# Sheet1.net
KiCad netlist of a schematic drawn in Altium Designer
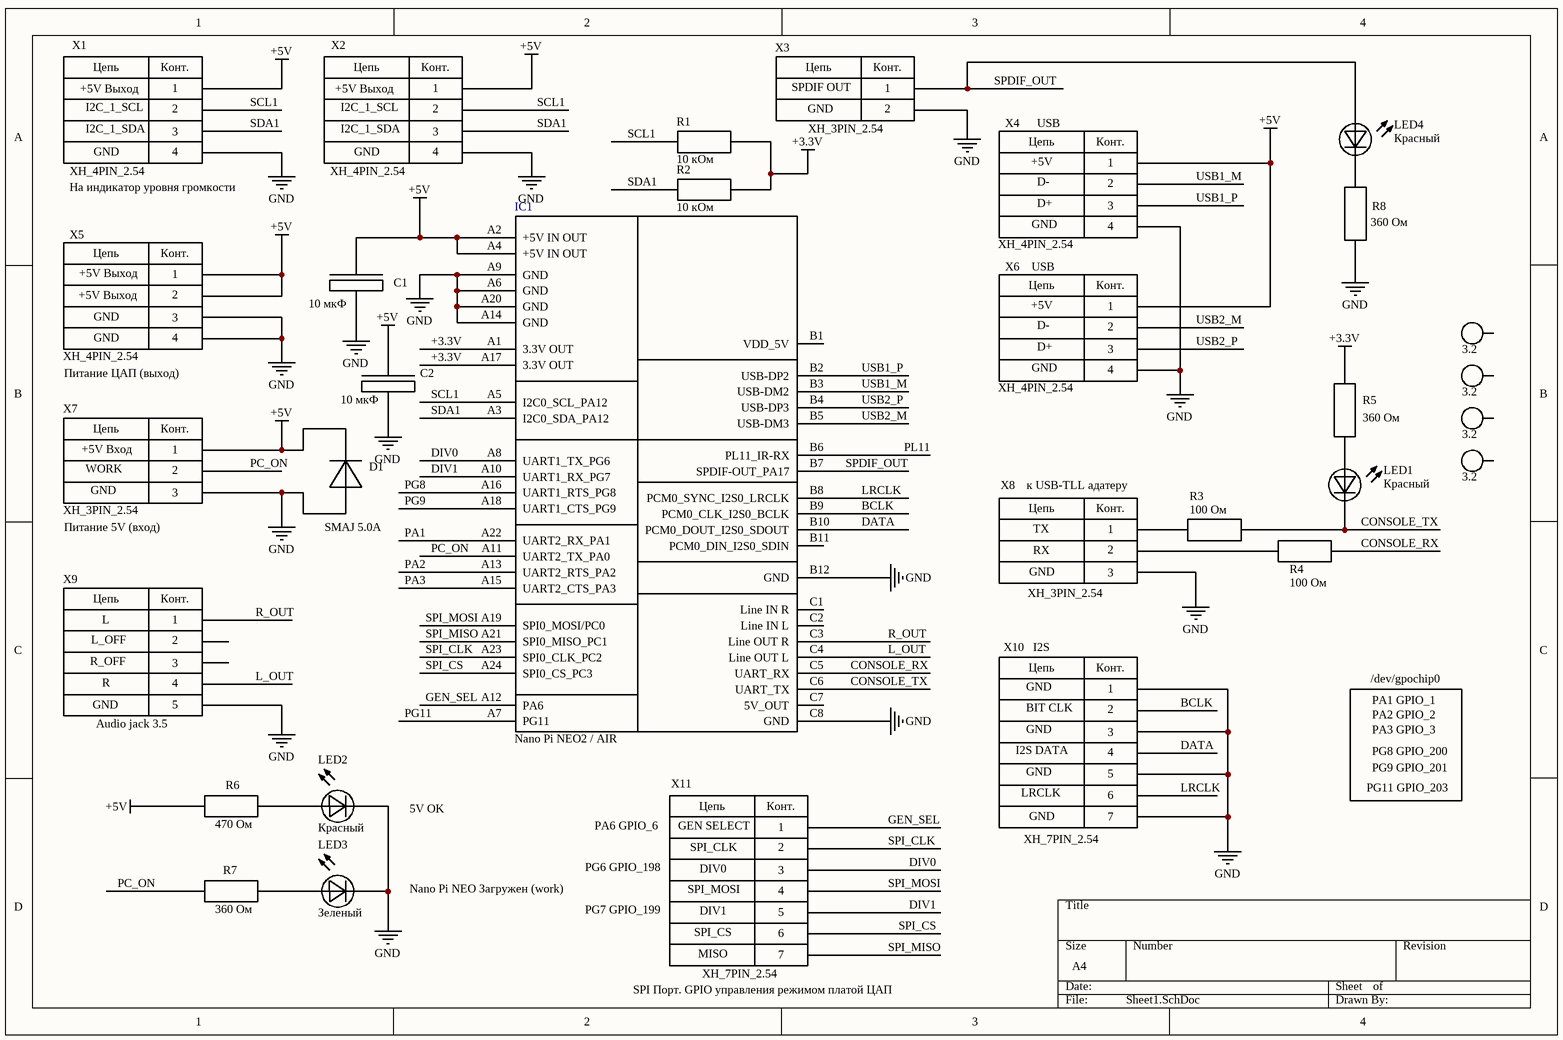
[diagram p0: Sheet1.SchDoc]

(export (version "E")
  (design (tool "Eeschema 10.0.6"))
  (components
    (comp (ref "C1")
      (value "10 мкФ")
      (footprint "Конденсатор SMD тантал 4x7")
      (libsource (lib "S83") (part "Конденсатор"))
    )
    (comp (ref "C2")
      (value "10 мкФ")
      (footprint "Конденсатор SMD тантал 4x7")
      (libsource (lib "S83") (part "Конденсатор"))
    )
    (comp (ref "D1") (value "SMAJ 5.0A") (footprint "Диод SS14") (libsource (lib "S83") (part "Диод")))
    (comp (ref "H1")
      (value "3.2")
      (footprint "Отверстие 3,2")
      (libsource (lib "S83") (part "Отверстие монтажное"))
    )
    (comp (ref "H2")
      (value "3.2")
      (footprint "Отверстие 3,2")
      (libsource (lib "S83") (part "Отверстие монтажное"))
    )
    (comp (ref "H3")
      (value "3.2")
      (footprint "Отверстие 3,2")
      (libsource (lib "S83") (part "Отверстие монтажное"))
    )
    (comp (ref "H4")
      (value "3.2")
      (footprint "Отверстие 3,2")
      (libsource (lib "S83") (part "Отверстие монтажное"))
    )
    (comp (ref "IC1")
      (value "Nano Pi NEO2 / AIR")
      (footprint "NANOPI_NEO")
      (libsource (lib "S83_IC") (part "NanoPi NEO"))
    )
    (comp (ref "LED1")
      (value "Красный")
      (footprint "Светодиод 3mm")
      (libsource (lib "S83") (part "Светодиод"))
    )
    (comp (ref "LED2")
      (value "Красный")
      (footprint "Светодиод 3mm")
      (libsource (lib "S83") (part "Светодиод"))
    )
    (comp (ref "LED3")
      (value "Зеленый")
      (footprint "Светодиод 3mm")
      (libsource (lib "S83") (part "Светодиод"))
    )
    (comp (ref "LED4")
      (value "Красный")
      (footprint "Светодиод 3mm")
      (libsource (lib "S83") (part "Светодиод"))
    )
    (comp (ref "R1")
      (value "10 кОм")
      (footprint "SMD 1206 Резистор")
      (libsource (lib "S83") (part "Резистор"))
    )
    (comp (ref "R2")
      (value "10 кОм")
      (footprint "SMD 1206 Резистор")
      (libsource (lib "S83") (part "Резистор"))
    )
    (comp (ref "R3")
      (value "100 Ом")
      (footprint "SMD 1206 Резистор")
      (libsource (lib "S83") (part "Резистор"))
    )
    (comp (ref "R4")
      (value "100 Ом")
      (footprint "SMD 1206 Резистор")
      (libsource (lib "S83") (part "Резистор"))
    )
    (comp (ref "R5")
      (value "360 Ом")
      (footprint "SMD 1206 Резистор")
      (libsource (lib "S83") (part "Резистор"))
    )
    (comp (ref "R6")
      (value "470 Ом")
      (footprint "SMD 1206 Резистор")
      (libsource (lib "S83") (part "Резистор"))
    )
    (comp (ref "R7")
      (value "360 Ом")
      (footprint "SMD 1206 Резистор")
      (libsource (lib "S83") (part "Резистор"))
    )
    (comp (ref "R8")
      (value "360 Ом")
      (footprint "SMD 1206 Резистор")
      (libsource (lib "S83") (part "Резистор"))
    )
    (comp (ref "X1")
      (value "XH_4PIN_2.54")
      (footprint "(1x4) PIN XH 2.54 HEADR")
      (libsource (lib "S83_connectors") (part "(1x4) pin XH 2.54 Header"))
    )
    (comp (ref "X2")
      (value "XH_4PIN_2.54")
      (footprint "(1x4) PIN XH 2.54 HEADR")
      (libsource (lib "S83_connectors") (part "(1x4) pin XH 2.54 Header"))
    )
    (comp (ref "X3")
      (value "XH_3PIN_2.54")
      (footprint "(1x2) PIN XH 2.54 header")
      (libsource (lib "S83_connectors") (part "(1x2)pin 2.54 Header"))
    )
    (comp (ref "X4")
      (value "XH_4PIN_2.54")
      (footprint "(1x4) PIN XH 2.54 HEADR")
      (libsource (lib "S83_connectors") (part "(1x4) pin XH 2.54 Header"))
    )
    (comp (ref "X5")
      (value "XH_4PIN_2.54")
      (footprint "(1x4) PIN XH 2.54 HEADR")
      (libsource (lib "S83_connectors") (part "(1x4) pin XH 2.54 Header"))
    )
    (comp (ref "X6")
      (value "XH_4PIN_2.54")
      (footprint "(1x4) PIN XH 2.54 HEADR")
      (libsource (lib "S83_connectors") (part "(1x4) pin XH 2.54 Header"))
    )
    (comp (ref "X7")
      (value "XH_3PIN_2.54")
      (footprint "(1x3) PIN XH 2.54 HEADR")
      (libsource (lib "S83_connectors") (part "(1x3)pin 2.54 Header"))
    )
    (comp (ref "X8")
      (value "XH_3PIN_2.54")
      (footprint "(1x3) PIN XH 2.54 HEADR")
      (libsource (lib "S83_connectors") (part "(1x3)pin 2.54 Header"))
    )
    (comp (ref "X9")
      (value "Audio jack 3.5")
      (footprint "3.5 Audio jack mama")
      (libsource (lib "S83_connectors") (part "3.5 Audio"))
    )
    (comp (ref "X10")
      (value "XH_7PIN_2.54")
      (footprint "(1x7) PIN XH 2.54 HEADR")
      (libsource (lib "S83_connectors") (part "(1x7) pin 2.54 Header"))
    )
    (comp (ref "X11")
      (value "XH_7PIN_2.54")
      (footprint "(1x7) PIN XH 2.54 HEADR")
      (libsource (lib "S83_connectors") (part "(1x7) pin 2.54 Header"))
    )
  )
  (nets
    (net (code "1") (name "+3.3V") (class "Default")
      (node (ref "IC1") (pin "A1") (pinfunction "3.3V_OUT_A1") (pintype "passive"))
      (node (ref "IC1") (pin "A17") (pinfunction "3.3V_OUT_A17") (pintype "passive"))
      (node (ref "R1") (pin "1") (pinfunction "left_1") (pintype "passive"))
      (node (ref "R2") (pin "1") (pinfunction "left_1") (pintype "passive"))
      (node (ref "R5") (pin "1") (pinfunction "left_1") (pintype "passive"))
    )
    (net (code "2") (name "+5V") (class "Default")
      (node (ref "C1") (pin "1") (pinfunction "1_1") (pintype "passive"))
      (node (ref "C2") (pin "1") (pinfunction "1_1") (pintype "passive"))
      (node (ref "D1") (pin "2") (pinfunction "K_2") (pintype "passive"))
      (node (ref "IC1") (pin "A2") (pinfunction "+5V_IN_OUT_A2") (pintype "passive"))
      (node (ref "IC1") (pin "A4") (pinfunction "+5V_IN_OUT_A4") (pintype "passive"))
      (node (ref "R6") (pin "2") (pinfunction "right_2") (pintype "passive"))
      (node (ref "X1") (pin "1") (pinfunction "1_1") (pintype "passive"))
      (node (ref "X2") (pin "1") (pinfunction "1_1") (pintype "passive"))
      (node (ref "X4") (pin "1") (pinfunction "1_1") (pintype "passive"))
      (node (ref "X5") (pin "1") (pinfunction "1_1") (pintype "passive"))
      (node (ref "X5") (pin "2") (pinfunction "2_2") (pintype "passive"))
      (node (ref "X6") (pin "1") (pinfunction "1_1") (pintype "passive"))
      (node (ref "X7") (pin "1") (pinfunction "1_1") (pintype "passive"))
    )
    (net (code "3") (name "/BCLK") (class "Default")
      (node (ref "IC1") (pin "B9") (pinfunction "PCM0_CLK_I2S0_BCLK_B9") (pintype "passive"))
      (node (ref "X10") (pin "2") (pinfunction "2_2") (pintype "passive"))
    )
    (net (code "4") (name "/CONSOLE_RX") (class "Default")
      (node (ref "IC1") (pin "C5") (pinfunction "UART_RX_C5") (pintype "passive"))
      (node (ref "R4") (pin "1") (pinfunction "left_1") (pintype "passive"))
    )
    (net (code "5") (name "/CONSOLE_TX") (class "Default")
      (node (ref "IC1") (pin "C6") (pinfunction "UART_TX_C6") (pintype "passive"))
      (node (ref "LED1") (pin "2") (pinfunction "K_2") (pintype "passive"))
      (node (ref "R3") (pin "1") (pinfunction "left_1") (pintype "passive"))
    )
    (net (code "8") (name "/DATA") (class "Default")
      (node (ref "IC1") (pin "B10") (pinfunction "PCM0_DOUT_I2S0_SDOUT_B10") (pintype "passive"))
      (node (ref "X10") (pin "4") (pinfunction "4_4") (pintype "passive"))
    )
    (net (code "9") (name "/DIV0") (class "Default")
      (node (ref "IC1") (pin "A8") (pinfunction "UART1_TX_PG6_A8") (pintype "passive"))
      (node (ref "X11") (pin "3") (pinfunction "3_3") (pintype "passive"))
    )
    (net (code "10") (name "/DIV1") (class "Default")
      (node (ref "IC1") (pin "A10") (pinfunction "UART1_RX_PG7_A10") (pintype "passive"))
      (node (ref "X11") (pin "5") (pinfunction "5_5") (pintype "passive"))
    )
    (net (code "11") (name "/GEN_SEL") (class "Default")
      (node (ref "IC1") (pin "A12") (pinfunction "PA6_A12") (pintype "passive"))
      (node (ref "X11") (pin "1") (pinfunction "1_1") (pintype "passive"))
    )
    (net (code "14") (name "/LRCLK") (class "Default")
      (node (ref "IC1") (pin "B8") (pinfunction "PCM0_SYNC_I2S0_LRCLK_B8") (pintype "passive"))
      (node (ref "X10") (pin "6") (pinfunction "6_6") (pintype "passive"))
    )
    (net (code "15") (name "/L_OUT") (class "Default")
      (node (ref "IC1") (pin "C4") (pinfunction "Line_OUT_L_C4") (pintype "passive"))
      (node (ref "X9") (pin "4") (pinfunction "4_4") (pintype "passive"))
    )
    (net (code "16") (name "/PA1") (class "Default")
      (node (ref "IC1") (pin "A22") (pinfunction "UART2_RX_PA1_A22") (pintype "passive"))
    )
    (net (code "17") (name "/PA2") (class "Default")
      (node (ref "IC1") (pin "A13") (pinfunction "UART2_RTS_PA2_A13") (pintype "passive"))
    )
    (net (code "18") (name "/PA3") (class "Default")
      (node (ref "IC1") (pin "A15") (pinfunction "UART2_CTS_PA3_A15") (pintype "passive"))
    )
    (net (code "19") (name "/PC_ON") (class "Default")
      (node (ref "IC1") (pin "A11") (pinfunction "UART2_TX_PA0_A11") (pintype "passive"))
      (node (ref "R7") (pin "2") (pinfunction "right_2") (pintype "passive"))
      (node (ref "X7") (pin "2") (pinfunction "2_2") (pintype "passive"))
    )
    (net (code "20") (name "/PG8") (class "Default")
      (node (ref "IC1") (pin "A16") (pinfunction "UART1_RTS_PG8_A16") (pintype "passive"))
    )
    (net (code "21") (name "/PG9") (class "Default")
      (node (ref "IC1") (pin "A18") (pinfunction "UART1_CTS_PG9_A18") (pintype "passive"))
    )
    (net (code "22") (name "/PG11") (class "Default")
      (node (ref "IC1") (pin "A7") (pinfunction "PG11_A7") (pintype "passive"))
    )
    (net (code "23") (name "/PL11") (class "Default")
      (node (ref "IC1") (pin "B6") (pinfunction "PL11_IR-RX_B6") (pintype "passive"))
    )
    (net (code "24") (name "/R_OUT") (class "Default")
      (node (ref "IC1") (pin "C3") (pinfunction "Line_OUT_R_C3") (pintype "passive"))
      (node (ref "X9") (pin "1") (pinfunction "1_1") (pintype "passive"))
    )
    (net (code "25") (name "/SCL1") (class "Default")
      (node (ref "IC1") (pin "A5") (pinfunction "I2C0_SCL_PA12_A5") (pintype "passive"))
      (node (ref "R1") (pin "2") (pinfunction "right_2") (pintype "passive"))
      (node (ref "X1") (pin "2") (pinfunction "2_2") (pintype "passive"))
      (node (ref "X2") (pin "2") (pinfunction "2_2") (pintype "passive"))
    )
    (net (code "26") (name "/SDA1") (class "Default")
      (node (ref "IC1") (pin "A3") (pinfunction "I2C0_SDA_PA12_A3") (pintype "passive"))
      (node (ref "R2") (pin "2") (pinfunction "right_2") (pintype "passive"))
      (node (ref "X1") (pin "3") (pinfunction "3_3") (pintype "passive"))
      (node (ref "X2") (pin "3") (pinfunction "3_3") (pintype "passive"))
    )
    (net (code "27") (name "/SPDIF_OUT") (class "Default")
      (node (ref "IC1") (pin "B7") (pinfunction "SPDIF-OUT_PA17_B7") (pintype "passive"))
      (node (ref "LED4") (pin "1") (pinfunction "А_1") (pintype "passive"))
      (node (ref "X3") (pin "1") (pinfunction "1_1") (pintype "passive"))
    )
    (net (code "28") (name "/SPI_CLK") (class "Default")
      (node (ref "IC1") (pin "A23") (pinfunction "SPI0_CLK_PC2_A23") (pintype "passive"))
      (node (ref "X11") (pin "2") (pinfunction "2_2") (pintype "passive"))
    )
    (net (code "29") (name "/SPI_CS") (class "Default")
      (node (ref "IC1") (pin "A24") (pinfunction "SPI0_CS_PC3_A24") (pintype "passive"))
      (node (ref "X11") (pin "6") (pinfunction "6_6") (pintype "passive"))
    )
    (net (code "30") (name "/SPI_MISO") (class "Default")
      (node (ref "IC1") (pin "A21") (pinfunction "SPI0_MISO_PC1_A21") (pintype "passive"))
      (node (ref "X11") (pin "7") (pinfunction "7_7") (pintype "passive"))
    )
    (net (code "31") (name "/SPI_MOSI") (class "Default")
      (node (ref "IC1") (pin "A19") (pinfunction "SPI0_MOSI/PС0_A19") (pintype "passive"))
      (node (ref "X11") (pin "4") (pinfunction "4_4") (pintype "passive"))
    )
    (net (code "32") (name "/USB1_M") (class "Default")
      (node (ref "IC1") (pin "B3") (pinfunction "USB-DM2_B3") (pintype "passive"))
      (node (ref "X4") (pin "2") (pinfunction "2_2") (pintype "passive"))
    )
    (net (code "33") (name "/USB1_P") (class "Default")
      (node (ref "IC1") (pin "B2") (pinfunction "USB-DP2_B2") (pintype "passive"))
      (node (ref "X4") (pin "3") (pinfunction "3_3") (pintype "passive"))
    )
    (net (code "34") (name "/USB2_M") (class "Default")
      (node (ref "IC1") (pin "B5") (pinfunction "USB-DM3_B5") (pintype "passive"))
      (node (ref "X6") (pin "2") (pinfunction "2_2") (pintype "passive"))
    )
    (net (code "35") (name "/USB2_P") (class "Default")
      (node (ref "IC1") (pin "B4") (pinfunction "USB-DP3_B4") (pintype "passive"))
      (node (ref "X6") (pin "3") (pinfunction "3_3") (pintype "passive"))
    )
    (net (code "36") (name "GND") (class "Default")
      (node (ref "C1") (pin "2") (pinfunction "2_2") (pintype "passive"))
      (node (ref "C2") (pin "2") (pinfunction "2_2") (pintype "passive"))
      (node (ref "D1") (pin "1") (pinfunction "А_1") (pintype "passive"))
      (node (ref "IC1") (pin "A14") (pinfunction "GND_A14") (pintype "passive"))
      (node (ref "IC1") (pin "A20") (pinfunction "GND_A20") (pintype "passive"))
      (node (ref "IC1") (pin "A6") (pinfunction "GND_A6") (pintype "passive"))
      (node (ref "IC1") (pin "A9") (pinfunction "GND_A9") (pintype "passive"))
      (node (ref "IC1") (pin "B12") (pinfunction "GND_B12") (pintype "passive"))
      (node (ref "IC1") (pin "C8") (pinfunction "GND_C8") (pintype "passive"))
      (node (ref "LED2") (pin "2") (pinfunction "K_2") (pintype "passive"))
      (node (ref "LED3") (pin "2") (pinfunction "K_2") (pintype "passive"))
      (node (ref "R8") (pin "2") (pinfunction "right_2") (pintype "passive"))
      (node (ref "X1") (pin "4") (pinfunction "4_4") (pintype "passive"))
      (node (ref "X10") (pin "1") (pinfunction "1_1") (pintype "passive"))
      (node (ref "X10") (pin "3") (pinfunction "3_3") (pintype "passive"))
      (node (ref "X10") (pin "5") (pinfunction "5_5") (pintype "passive"))
      (node (ref "X10") (pin "7") (pinfunction "7_7") (pintype "passive"))
      (node (ref "X2") (pin "4") (pinfunction "4_4") (pintype "passive"))
      (node (ref "X3") (pin "2") (pinfunction "2_2") (pintype "passive"))
      (node (ref "X4") (pin "4") (pinfunction "4_4") (pintype "passive"))
      (node (ref "X5") (pin "3") (pinfunction "3_3") (pintype "passive"))
      (node (ref "X5") (pin "4") (pinfunction "4_4") (pintype "passive"))
      (node (ref "X6") (pin "4") (pinfunction "4_4") (pintype "passive"))
      (node (ref "X7") (pin "3") (pinfunction "3_3") (pintype "passive"))
      (node (ref "X8") (pin "3") (pinfunction "3_3") (pintype "passive"))
      (node (ref "X9") (pin "5") (pinfunction "5_5") (pintype "passive"))
    )
    (net (code "37") (name "Net-(LED1-А)") (class "Default")
      (node (ref "LED1") (pin "1") (pinfunction "А_1") (pintype "passive"))
      (node (ref "R5") (pin "2") (pinfunction "right_2") (pintype "passive"))
    )
    (net (code "38") (name "Net-(LED2-А)") (class "Default")
      (node (ref "LED2") (pin "1") (pinfunction "А_1") (pintype "passive"))
      (node (ref "R6") (pin "1") (pinfunction "left_1") (pintype "passive"))
    )
    (net (code "39") (name "Net-(LED3-А)") (class "Default")
      (node (ref "LED3") (pin "1") (pinfunction "А_1") (pintype "passive"))
      (node (ref "R7") (pin "1") (pinfunction "left_1") (pintype "passive"))
    )
    (net (code "40") (name "Net-(LED4-K)") (class "Default")
      (node (ref "LED4") (pin "2") (pinfunction "K_2") (pintype "passive"))
      (node (ref "R8") (pin "1") (pinfunction "left_1") (pintype "passive"))
    )
    (net (code "41") (name "Net-(R3-right)") (class "Default")
      (node (ref "R3") (pin "2") (pinfunction "right_2") (pintype "passive"))
      (node (ref "X8") (pin "1") (pinfunction "1_1") (pintype "passive"))
    )
    (net (code "42") (name "Net-(R4-right)") (class "Default")
      (node (ref "R4") (pin "2") (pinfunction "right_2") (pintype "passive"))
      (node (ref "X8") (pin "2") (pinfunction "2_2") (pintype "passive"))
    )
    (net (code "43") (name "unconnected-(H1-Pad1)") (class "Default")
      (node (ref "H1") (pin "1") (pinfunction "1_1") (pintype "passive"))
    )
    (net (code "44") (name "unconnected-(H2-Pad1)") (class "Default")
      (node (ref "H2") (pin "1") (pinfunction "1_1") (pintype "passive"))
    )
    (net (code "45") (name "unconnected-(H3-Pad1)") (class "Default")
      (node (ref "H3") (pin "1") (pinfunction "1_1") (pintype "passive"))
    )
    (net (code "46") (name "unconnected-(H4-Pad1)") (class "Default")
      (node (ref "H4") (pin "1") (pinfunction "1_1") (pintype "passive"))
    )
    (net (code "47") (name "unconnected-(IC1-5V_OUT-PadC7)") (class "Default")
      (node (ref "IC1") (pin "C7") (pinfunction "5V_OUT_C7") (pintype "passive"))
    )
    (net (code "48") (name "unconnected-(IC1-Line_IN_L-PadC2)") (class "Default")
      (node (ref "IC1") (pin "C2") (pinfunction "Line_IN_L_C2") (pintype "passive"))
    )
    (net (code "49") (name "unconnected-(IC1-Line_IN_R-PadC1)") (class "Default")
      (node (ref "IC1") (pin "C1") (pinfunction "Line_IN_R_C1") (pintype "passive"))
    )
    (net (code "50") (name "unconnected-(IC1-PCM0_DIN_I2S0_SDIN-PadB11)") (class "Default")
      (node (ref "IC1") (pin "B11") (pinfunction "PCM0_DIN_I2S0_SDIN_B11") (pintype "passive"))
    )
    (net (code "51") (name "unconnected-(IC1-VDD_5V-PadB1)") (class "Default")
      (node (ref "IC1") (pin "B1") (pinfunction "VDD_5V_B1") (pintype "passive"))
    )
    (net (code "52") (name "unconnected-(X9-Pad2)") (class "Default")
      (node (ref "X9") (pin "2") (pinfunction "2_2") (pintype "passive"))
    )
    (net (code "53") (name "unconnected-(X9-Pad3)") (class "Default")
      (node (ref "X9") (pin "3") (pinfunction "3_3") (pintype "passive"))
    )
  )
)
